# feederschematic.net
KiCad netlist of a schematic drawn in EAGLE
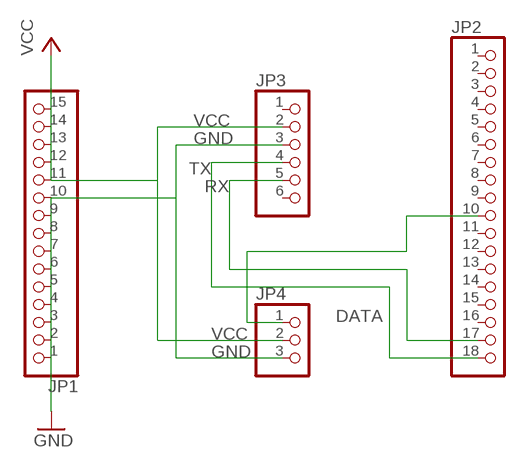
[diagram p0: schematic, sheet 1]

(export (version "E")
  (design (tool "Eeschema 10.0.6"))
  (components
    (comp (ref "JP1")
      (value "PINHD-1X15")
      (footprint "eagle-import:1X15")
      (libsource (lib "eagle-import") (part "PINHD-1X15"))
    )
    (comp (ref "JP2")
      (value "PINHD-1X18")
      (footprint "eagle-import:1X18")
      (libsource (lib "eagle-import") (part "PINHD-1X18"))
    )
    (comp (ref "JP3")
      (value "PINHD-1X6")
      (footprint "eagle-import:1X06")
      (libsource (lib "eagle-import") (part "PINHD-1X6"))
    )
    (comp (ref "JP4")
      (value "PINHD-1X3")
      (footprint "eagle-import:1X03")
      (libsource (lib "eagle-import") (part "PINHD-1X3"))
    )
  )
  (nets
    (net (code "1") (name "/DATA") (class "Default")
      (node (ref "JP2") (pin "10") (pinfunction "10_10") (pintype "passive"))
      (node (ref "JP4") (pin "1") (pinfunction "1_1") (pintype "passive"))
    )
    (net (code "2") (name "/RX") (class "Default")
      (node (ref "JP2") (pin "17") (pinfunction "17_17") (pintype "passive"))
      (node (ref "JP3") (pin "5") (pinfunction "5_5") (pintype "passive"))
    )
    (net (code "3") (name "/TX") (class "Default")
      (node (ref "JP2") (pin "18") (pinfunction "18_18") (pintype "passive"))
      (node (ref "JP3") (pin "4") (pinfunction "4_4") (pintype "passive"))
    )
    (net (code "4") (name "GND") (class "Default")
      (node (ref "JP1") (pin "10") (pinfunction "10_10") (pintype "passive"))
      (node (ref "JP3") (pin "3") (pinfunction "3_3") (pintype "passive"))
      (node (ref "JP4") (pin "3") (pinfunction "3_3") (pintype "passive"))
    )
    (net (code "5") (name "VCC") (class "Default")
      (node (ref "JP1") (pin "11") (pinfunction "11_11") (pintype "passive"))
      (node (ref "JP3") (pin "2") (pinfunction "2_2") (pintype "passive"))
      (node (ref "JP4") (pin "2") (pinfunction "2_2") (pintype "passive"))
    )
    (net (code "6") (name "unconnected-(JP1-Pad1)") (class "Default")
      (node (ref "JP1") (pin "1") (pinfunction "1_1") (pintype "passive"))
    )
    (net (code "7") (name "unconnected-(JP1-Pad2)") (class "Default")
      (node (ref "JP1") (pin "2") (pinfunction "2_2") (pintype "passive"))
    )
    (net (code "8") (name "unconnected-(JP1-Pad3)") (class "Default")
      (node (ref "JP1") (pin "3") (pinfunction "3_3") (pintype "passive"))
    )
    (net (code "9") (name "unconnected-(JP1-Pad4)") (class "Default")
      (node (ref "JP1") (pin "4") (pinfunction "4_4") (pintype "passive"))
    )
    (net (code "10") (name "unconnected-(JP1-Pad5)") (class "Default")
      (node (ref "JP1") (pin "5") (pinfunction "5_5") (pintype "passive"))
    )
    (net (code "11") (name "unconnected-(JP1-Pad6)") (class "Default")
      (node (ref "JP1") (pin "6") (pinfunction "6_6") (pintype "passive"))
    )
    (net (code "12") (name "unconnected-(JP1-Pad7)") (class "Default")
      (node (ref "JP1") (pin "7") (pinfunction "7_7") (pintype "passive"))
    )
    (net (code "13") (name "unconnected-(JP1-Pad8)") (class "Default")
      (node (ref "JP1") (pin "8") (pinfunction "8_8") (pintype "passive"))
    )
    (net (code "14") (name "unconnected-(JP1-Pad9)") (class "Default")
      (node (ref "JP1") (pin "9") (pinfunction "9_9") (pintype "passive"))
    )
    (net (code "15") (name "unconnected-(JP1-Pad12)") (class "Default")
      (node (ref "JP1") (pin "12") (pinfunction "12_12") (pintype "passive"))
    )
    (net (code "16") (name "unconnected-(JP1-Pad13)") (class "Default")
      (node (ref "JP1") (pin "13") (pinfunction "13_13") (pintype "passive"))
    )
    (net (code "17") (name "unconnected-(JP1-Pad14)") (class "Default")
      (node (ref "JP1") (pin "14") (pinfunction "14_14") (pintype "passive"))
    )
    (net (code "18") (name "unconnected-(JP1-Pad15)") (class "Default")
      (node (ref "JP1") (pin "15") (pinfunction "15_15") (pintype "passive"))
    )
    (net (code "19") (name "unconnected-(JP2-Pad1)") (class "Default")
      (node (ref "JP2") (pin "1") (pinfunction "1_1") (pintype "passive"))
    )
    (net (code "20") (name "unconnected-(JP2-Pad2)") (class "Default")
      (node (ref "JP2") (pin "2") (pinfunction "2_2") (pintype "passive"))
    )
    (net (code "21") (name "unconnected-(JP2-Pad3)") (class "Default")
      (node (ref "JP2") (pin "3") (pinfunction "3_3") (pintype "passive"))
    )
    (net (code "22") (name "unconnected-(JP2-Pad4)") (class "Default")
      (node (ref "JP2") (pin "4") (pinfunction "4_4") (pintype "passive"))
    )
    (net (code "23") (name "unconnected-(JP2-Pad5)") (class "Default")
      (node (ref "JP2") (pin "5") (pinfunction "5_5") (pintype "passive"))
    )
    (net (code "24") (name "unconnected-(JP2-Pad6)") (class "Default")
      (node (ref "JP2") (pin "6") (pinfunction "6_6") (pintype "passive"))
    )
    (net (code "25") (name "unconnected-(JP2-Pad7)") (class "Default")
      (node (ref "JP2") (pin "7") (pinfunction "7_7") (pintype "passive"))
    )
    (net (code "26") (name "unconnected-(JP2-Pad8)") (class "Default")
      (node (ref "JP2") (pin "8") (pinfunction "8_8") (pintype "passive"))
    )
    (net (code "27") (name "unconnected-(JP2-Pad9)") (class "Default")
      (node (ref "JP2") (pin "9") (pinfunction "9_9") (pintype "passive"))
    )
    (net (code "28") (name "unconnected-(JP2-Pad11)") (class "Default")
      (node (ref "JP2") (pin "11") (pinfunction "11_11") (pintype "passive"))
    )
    (net (code "29") (name "unconnected-(JP2-Pad12)") (class "Default")
      (node (ref "JP2") (pin "12") (pinfunction "12_12") (pintype "passive"))
    )
    (net (code "30") (name "unconnected-(JP2-Pad13)") (class "Default")
      (node (ref "JP2") (pin "13") (pinfunction "13_13") (pintype "passive"))
    )
    (net (code "31") (name "unconnected-(JP2-Pad14)") (class "Default")
      (node (ref "JP2") (pin "14") (pinfunction "14_14") (pintype "passive"))
    )
    (net (code "32") (name "unconnected-(JP2-Pad15)") (class "Default")
      (node (ref "JP2") (pin "15") (pinfunction "15_15") (pintype "passive"))
    )
    (net (code "33") (name "unconnected-(JP2-Pad16)") (class "Default")
      (node (ref "JP2") (pin "16") (pinfunction "16_16") (pintype "passive"))
    )
    (net (code "34") (name "unconnected-(JP3-Pad1)") (class "Default")
      (node (ref "JP3") (pin "1") (pinfunction "1_1") (pintype "passive"))
    )
    (net (code "35") (name "unconnected-(JP3-Pad6)") (class "Default")
      (node (ref "JP3") (pin "6") (pinfunction "6_6") (pintype "passive"))
    )
  )
)
